# ADC_channel.net
KiCad netlist of a schematic drawn in Altium Designer
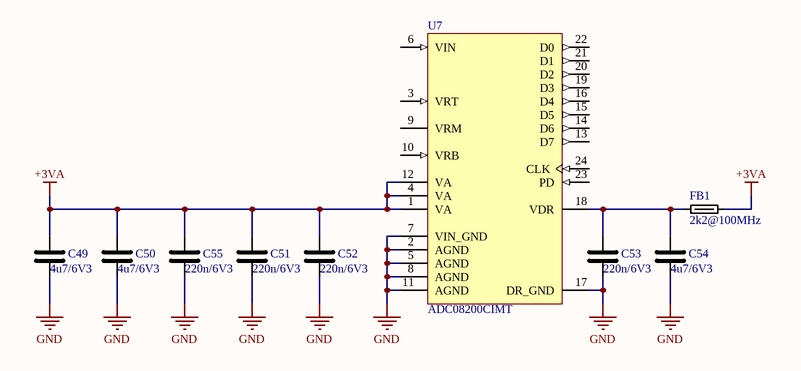
[diagram p0: ADC_channel.SchDoc]

(export (version "E")
  (design (tool "Eeschema 10.0.6"))
  (components
    (comp (ref "C49") (value "4u7/6V3") (footprint "C0805_N") (libsource (lib "niceCircuits") (part "C")))
    (comp (ref "C50") (value "4u7/6V3") (footprint "C0805_N") (libsource (lib "niceCircuits") (part "C")))
    (comp (ref "C51") (value "220n/6V3") (footprint "C0402_N") (libsource (lib "niceCircuits") (part "C")))
    (comp (ref "C52") (value "220n/6V3") (footprint "C0402_N") (libsource (lib "niceCircuits") (part "C")))
    (comp (ref "C53") (value "220n/6V3") (footprint "C0402_N") (libsource (lib "niceCircuits") (part "C")))
    (comp (ref "C54") (value "4u7/6V3") (footprint "C0805_N") (libsource (lib "niceCircuits") (part "C")))
    (comp (ref "C55") (value "220n/6V3") (footprint "C0402_N") (libsource (lib "niceCircuits") (part "C")))
    (comp (ref "FB1")
      (value "2k2@100MHz")
      (footprint "L0805_N")
      (description "Ferrite Bead, 0805, 2200R@100MHz, 0.8R@DC, 200mA max.")
      (fields (field (name "Comment") "HZ0805B222R-10"))
      (libsource (lib "Ferrite") (part "HZ0805B222R-10"))
    )
    (comp (ref "U7")
      (value "ADC08200CIMT")
      (footprint "National_TSSOP24_N")
      (libsource (lib "niceCircuits") (part "ADC08200CIMT"))
    )
  )
  (nets
    (net (code "1") (name "+3VA") (class "Default")
      (node (ref "C49") (pin "2") (pinfunction "2_2") (pintype "passive"))
      (node (ref "C50") (pin "2") (pinfunction "2_2") (pintype "passive"))
      (node (ref "C51") (pin "2") (pinfunction "2_2") (pintype "passive"))
      (node (ref "C52") (pin "2") (pinfunction "2_2") (pintype "passive"))
      (node (ref "C55") (pin "2") (pinfunction "2_2") (pintype "passive"))
      (node (ref "FB1") (pin "2") (pinfunction "2_2") (pintype "passive"))
      (node (ref "U7") (pin "1") (pinfunction "VA_1") (pintype "power_in"))
      (node (ref "U7") (pin "12") (pinfunction "VA_12") (pintype "power_in"))
      (node (ref "U7") (pin "4") (pinfunction "VA_4") (pintype "power_in"))
    )
    (net (code "2") (name "GND") (class "Default")
      (node (ref "C49") (pin "1") (pinfunction "1_1") (pintype "passive"))
      (node (ref "C50") (pin "1") (pinfunction "1_1") (pintype "passive"))
      (node (ref "C51") (pin "1") (pinfunction "1_1") (pintype "passive"))
      (node (ref "C52") (pin "1") (pinfunction "1_1") (pintype "passive"))
      (node (ref "C53") (pin "1") (pinfunction "1_1") (pintype "passive"))
      (node (ref "C54") (pin "1") (pinfunction "1_1") (pintype "passive"))
      (node (ref "C55") (pin "1") (pinfunction "1_1") (pintype "passive"))
      (node (ref "U7") (pin "11") (pinfunction "AGND_11") (pintype "power_in"))
      (node (ref "U7") (pin "17") (pinfunction "DR_GND_17") (pintype "power_in"))
      (node (ref "U7") (pin "2") (pinfunction "AGND_2") (pintype "power_in"))
      (node (ref "U7") (pin "5") (pinfunction "AGND_5") (pintype "power_in"))
      (node (ref "U7") (pin "7") (pinfunction "VIN_GND_7") (pintype "power_in"))
      (node (ref "U7") (pin "8") (pinfunction "AGND_8") (pintype "power_in"))
    )
    (net (code "3") (name "Net-(U7-VDR)") (class "Default")
      (node (ref "C53") (pin "2") (pinfunction "2_2") (pintype "passive"))
      (node (ref "C54") (pin "2") (pinfunction "2_2") (pintype "passive"))
      (node (ref "FB1") (pin "1") (pinfunction "1_1") (pintype "passive"))
      (node (ref "U7") (pin "18") (pinfunction "VDR_18") (pintype "power_in"))
    )
    (net (code "4") (name "unconnected-(U7-CLK-Pad24)") (class "Default")
      (node (ref "U7") (pin "24") (pinfunction "CLK_24") (pintype "input"))
    )
    (net (code "5") (name "unconnected-(U7-D0-Pad22)") (class "Default")
      (node (ref "U7") (pin "22") (pinfunction "D0_22") (pintype "output"))
    )
    (net (code "6") (name "unconnected-(U7-D1-Pad21)") (class "Default")
      (node (ref "U7") (pin "21") (pinfunction "D1_21") (pintype "output"))
    )
    (net (code "7") (name "unconnected-(U7-D2-Pad20)") (class "Default")
      (node (ref "U7") (pin "20") (pinfunction "D2_20") (pintype "output"))
    )
    (net (code "8") (name "unconnected-(U7-D3-Pad19)") (class "Default")
      (node (ref "U7") (pin "19") (pinfunction "D3_19") (pintype "output"))
    )
    (net (code "9") (name "unconnected-(U7-D4-Pad16)") (class "Default")
      (node (ref "U7") (pin "16") (pinfunction "D4_16") (pintype "output"))
    )
    (net (code "10") (name "unconnected-(U7-D5-Pad15)") (class "Default")
      (node (ref "U7") (pin "15") (pinfunction "D5_15") (pintype "output"))
    )
    (net (code "11") (name "unconnected-(U7-D6-Pad14)") (class "Default")
      (node (ref "U7") (pin "14") (pinfunction "D6_14") (pintype "output"))
    )
    (net (code "12") (name "unconnected-(U7-D7-Pad13)") (class "Default")
      (node (ref "U7") (pin "13") (pinfunction "D7_13") (pintype "output"))
    )
    (net (code "13") (name "unconnected-(U7-PD-Pad23)") (class "Default")
      (node (ref "U7") (pin "23") (pinfunction "PD_23") (pintype "input"))
    )
    (net (code "14") (name "unconnected-(U7-VIN-Pad6)") (class "Default")
      (node (ref "U7") (pin "6") (pinfunction "VIN_6") (pintype "input"))
    )
    (net (code "15") (name "unconnected-(U7-VRB-Pad10)") (class "Default")
      (node (ref "U7") (pin "10") (pinfunction "VRB_10") (pintype "input"))
    )
    (net (code "16") (name "unconnected-(U7-VRM-Pad9)") (class "Default")
      (node (ref "U7") (pin "9") (pinfunction "VRM_9") (pintype "passive"))
    )
    (net (code "17") (name "unconnected-(U7-VRT-Pad3)") (class "Default")
      (node (ref "U7") (pin "3") (pinfunction "VRT_3") (pintype "input"))
    )
  )
)
